# B45160514D.net
KiCad netlist of a schematic drawn in Altium Designer
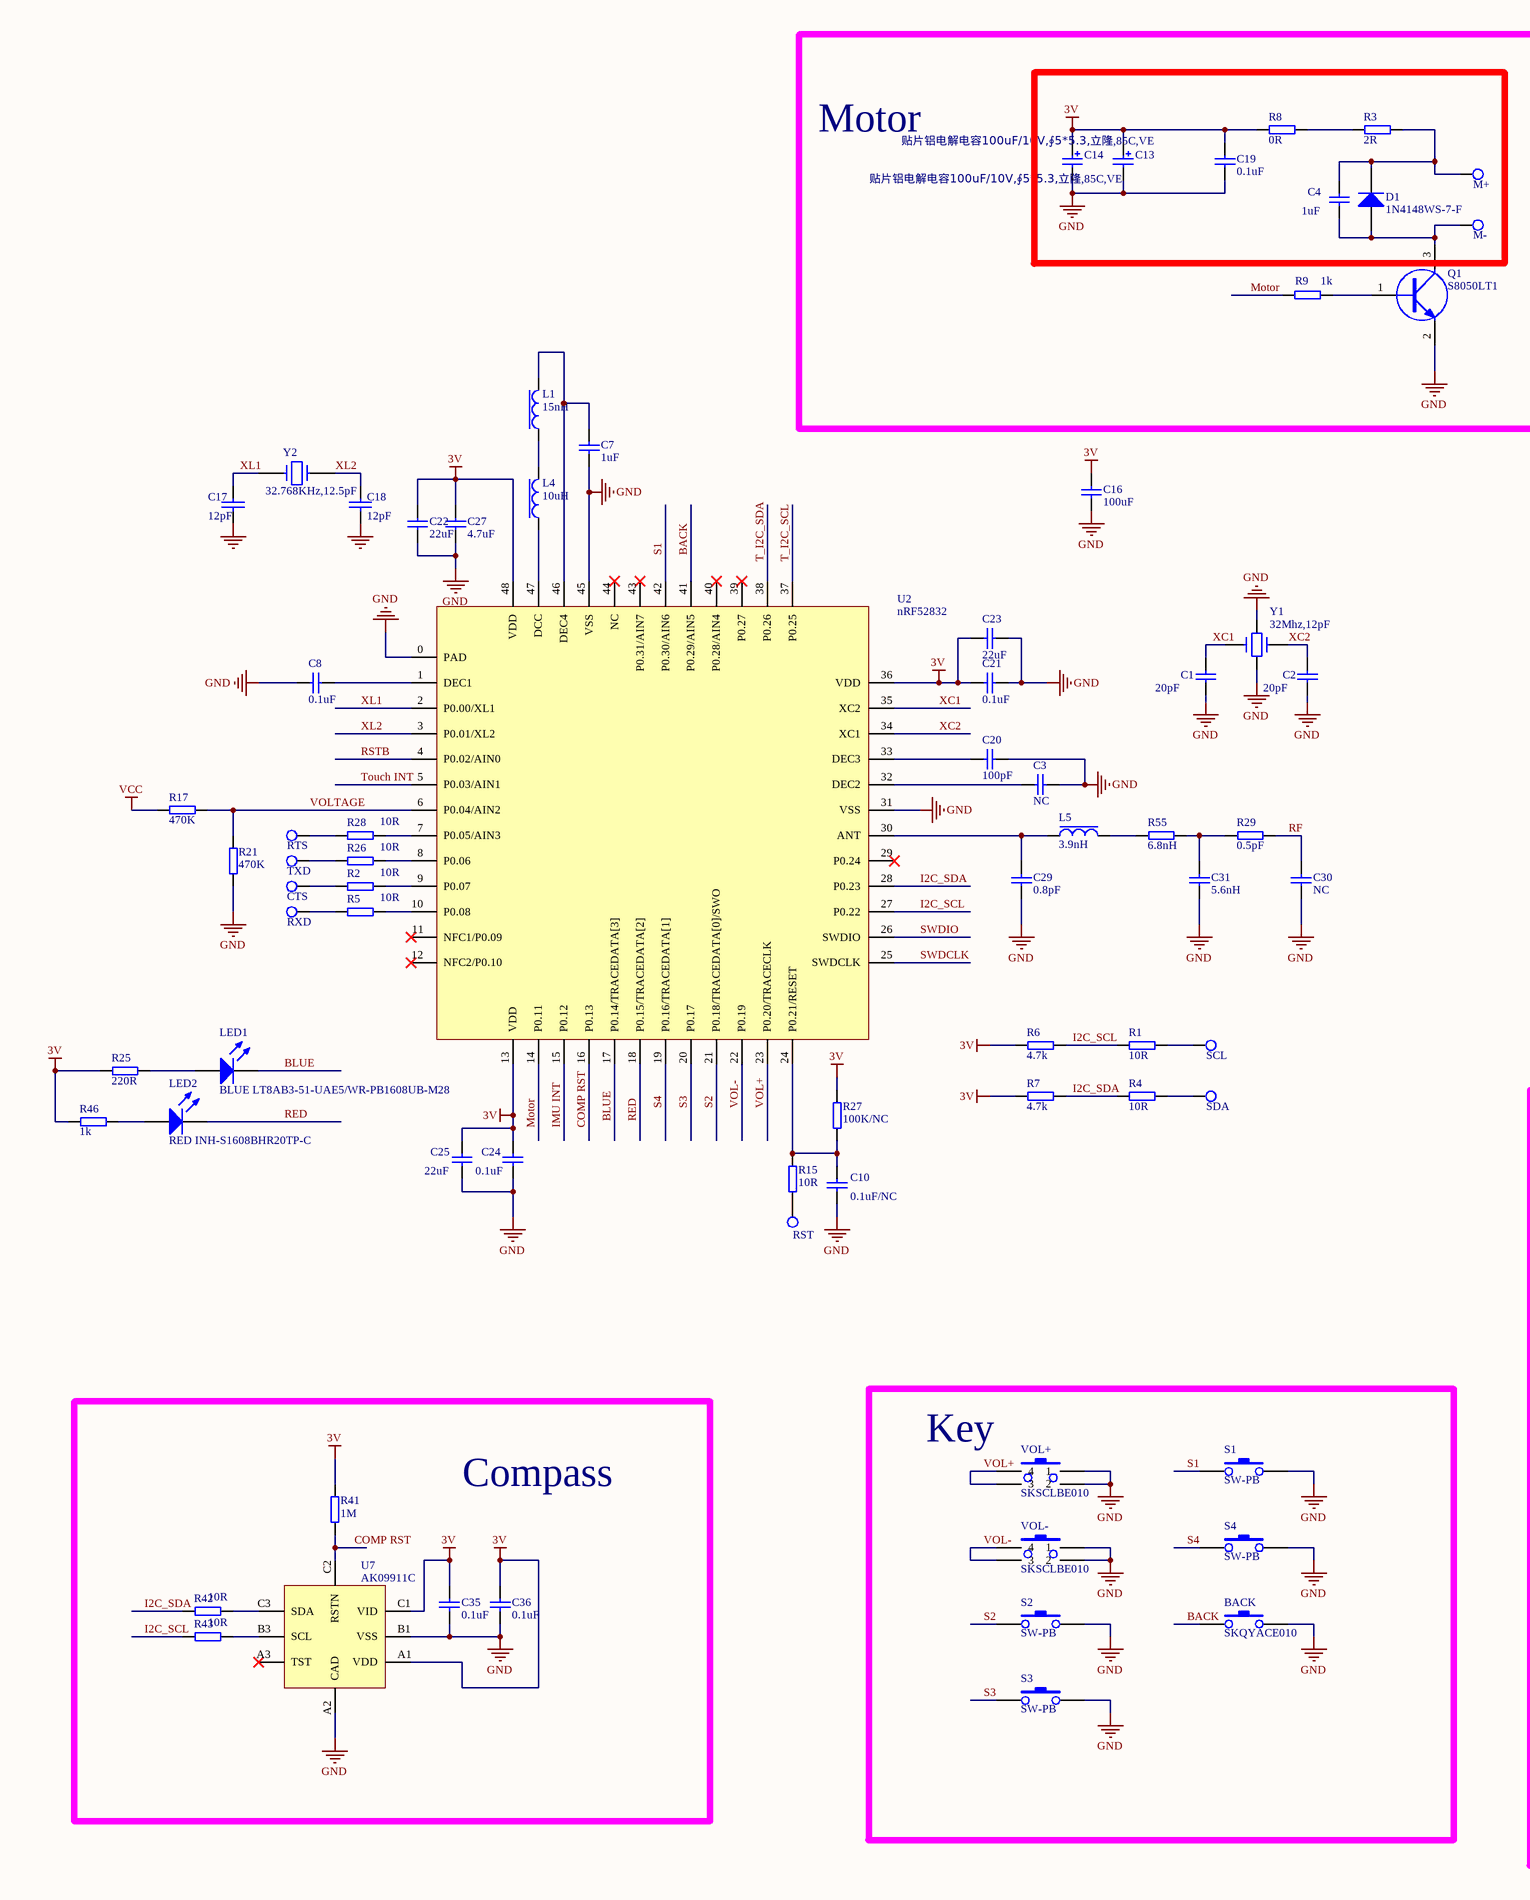
[diagram p0: B45160514D.SCHDOC, left]
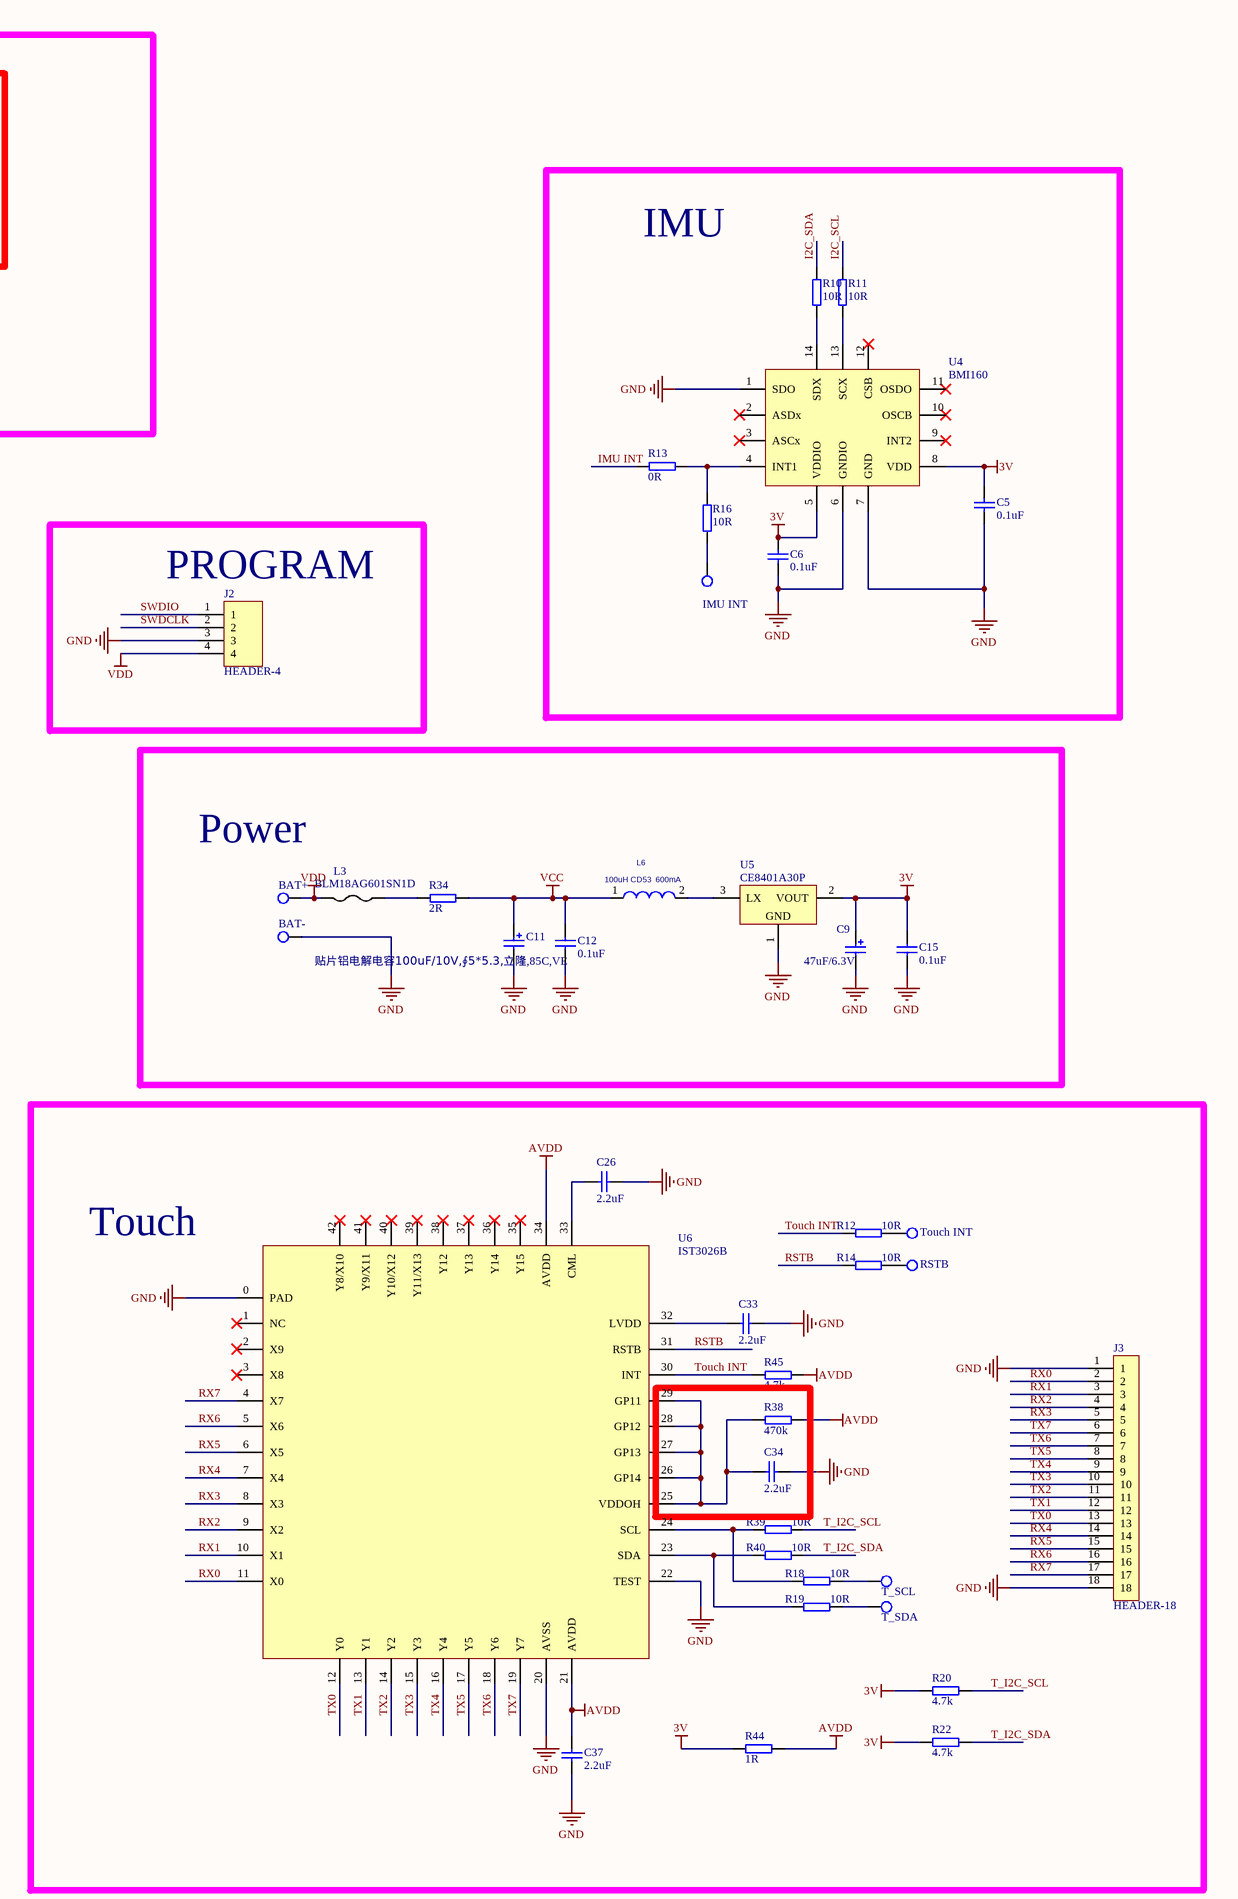
[diagram p1: B45160514D.SCHDOC, right]

(export (version "E")
  (design (tool "Eeschema 10.0.6"))
  (components
    (comp (ref "BACK") (value "SKQYACE010") (footprint "SKQYACE010") (libsource (lib "dusun") (part "SW-PB")))
    (comp (ref "BAT+") (value "TAP") (footprint "BAT") (libsource (lib "*") (part "TAP")))
    (comp (ref "BAT-") (value "TAP") (footprint "BAT") (libsource (lib "*") (part "TAP")))
    (comp (ref "C1") (value "20pF") (footprint "C-0402") (libsource (lib "dusun01-SCH") (part "CAP")))
    (comp (ref "C2") (value "20pF") (footprint "C-0402") (libsource (lib "dusun01-SCH") (part "CAP")))
    (comp (ref "C3") (value "NC") (footprint "C-0402") (libsource (lib "dusun01-SCH") (part "CAP")))
    (comp (ref "C4") (value "1uF") (footprint "C-0402") (libsource (lib "dusun01-SCH") (part "CAP")))
    (comp (ref "C5")
      (value "0.1uF")
      (footprint "C-0402")
      (description "capacitor 27 pF NPO , +/- 2 %, SMD case 0603")
      (fields
        (field (name "MANUFACTURER") "Generic Components")
        (field (name "PUBLISHER") "Altium Hobart Technology Centre")
      )
      (libsource (lib "Miscellaneous Devices") (part "Cap"))
    )
    (comp (ref "C6")
      (value "0.1uF")
      (footprint "C-0402")
      (description "capacitor 27 pF NPO , +/- 2 %, SMD case 0603")
      (fields
        (field (name "MANUFACTURER") "Generic Components")
        (field (name "PUBLISHER") "Altium Hobart Technology Centre")
      )
      (libsource (lib "Miscellaneous Devices") (part "Cap"))
    )
    (comp (ref "C7") (value "1uF") (footprint "C-0603") (libsource (lib "dusun01-SCH") (part "CAP")))
    (comp (ref "C8") (value "0.1uF") (footprint "C-0402") (libsource (lib "dusun01-SCH") (part "CAP")))
    (comp (ref "C9") (value "47uF/6.3V") (footprint "C-1206") (libsource (lib "dusun01-SCH") (part "CAP E")))
    (comp (ref "C10") (value "0.1uF/NC") (footprint "C-0402") (libsource (lib "dusun01-SCH") (part "CAP")))
    (comp (ref "C11")
      (value "贴片铝电解电容100uF/10V,∮5*5.3,立隆,85C,VE")
      (footprint "CAP_ALUM-C")
      (libsource (lib "dusun01-SCH") (part "CAP E"))
    )
    (comp (ref "C12") (value "0.1uF") (footprint "C-0603") (libsource (lib "dusun01-SCH") (part "CAP")))
    (comp (ref "C13")
      (value "贴片铝电解电容100uF/10V,∮5*5.3,立隆,85C,VE")
      (footprint "CAP_ALUM-C")
      (libsource (lib "dusun01-SCH") (part "CAP E"))
    )
    (comp (ref "C14")
      (value "贴片铝电解电容100uF/10V,∮5*5.3,立隆,85C,VE")
      (footprint "CAP_ALUM-C")
      (libsource (lib "dusun01-SCH") (part "CAP E"))
    )
    (comp (ref "C15") (value "0.1uF") (footprint "C-0603") (libsource (lib "dusun01-SCH") (part "CAP")))
    (comp (ref "C16") (value "100uF") (footprint "C-1206") (libsource (lib "dusun01-SCH") (part "CAP")))
    (comp (ref "C17")
      (value "12pF")
      (footprint "dusun01-pcb:C-0402")
      (description "Capacitor")
      (libsource (lib "*") (part "CAP"))
    )
    (comp (ref "C18")
      (value "12pF")
      (footprint "dusun01-pcb:C-0402")
      (description "Capacitor")
      (libsource (lib "*") (part "CAP"))
    )
    (comp (ref "C19") (value "0.1uF") (footprint "C-0603") (libsource (lib "dusun01-SCH") (part "CAP")))
    (comp (ref "C20") (value "100pF") (footprint "C-0402") (libsource (lib "dusun01-SCH") (part "CAP")))
    (comp (ref "C21") (value "0.1uF") (footprint "C-0402") (libsource (lib "dusun01-SCH") (part "CAP")))
    (comp (ref "C22") (value "22uF") (footprint "C-0805") (libsource (lib "dusun01-SCH") (part "CAP")))
    (comp (ref "C23") (value "22uF") (footprint "C-0805") (libsource (lib "dusun01-SCH") (part "CAP")))
    (comp (ref "C24") (value "0.1uF") (footprint "C-0402") (libsource (lib "dusun01-SCH") (part "CAP")))
    (comp (ref "C25") (value "22uF") (footprint "C-0805") (libsource (lib "dusun01-SCH") (part "CAP")))
    (comp (ref "C26") (value "2.2uF") (footprint "C-0402") (libsource (lib "dusun01-SCH") (part "CAP")))
    (comp (ref "C27") (value "4.7uF") (footprint "C-0603") (libsource (lib "dusun01-SCH") (part "CAP")))
    (comp (ref "C29") (value "0.8pF") (footprint "C-0402") (libsource (lib "dusun01-SCH") (part "CAP")))
    (comp (ref "C30") (value "NC") (footprint "C-0402") (libsource (lib "dusun01-SCH") (part "CAP")))
    (comp (ref "C31") (value "5.6nH") (footprint "C-0402") (libsource (lib "dusun01-SCH") (part "CAP")))
    (comp (ref "C33") (value "2.2uF") (footprint "C-0402") (libsource (lib "dusun01-SCH") (part "CAP")))
    (comp (ref "C34") (value "2.2uF") (footprint "C-0402") (libsource (lib "dusun01-SCH") (part "CAP")))
    (comp (ref "C35")
      (value "0.1uF")
      (footprint "C-0402")
      (description "capacitor 27 pF NPO , +/- 2 %, SMD case 0603")
      (fields
        (field (name "MANUFACTURER") "Generic Components")
        (field (name "PUBLISHER") "Altium Hobart Technology Centre")
      )
      (libsource (lib "Miscellaneous Devices") (part "Cap"))
    )
    (comp (ref "C36")
      (value "0.1uF")
      (footprint "C-0402")
      (description "capacitor 27 pF NPO , +/- 2 %, SMD case 0603")
      (fields
        (field (name "MANUFACTURER") "Generic Components")
        (field (name "PUBLISHER") "Altium Hobart Technology Centre")
      )
      (libsource (lib "Miscellaneous Devices") (part "Cap"))
    )
    (comp (ref "C37") (value "2.2uF") (footprint "C-0402") (libsource (lib "dusun01-SCH") (part "CAP")))
    (comp (ref "CTS") (value "TAP") (footprint "TS-1.0") (libsource (lib "dusun01-SCH") (part "TAP")))
    (comp (ref "D1")
      (value "1N4148WS-7-F")
      (footprint "SOD-323")
      (libsource (lib "dusun01-SCH") (part "DIODE"))
    )
    (comp (ref "IMU INT") (value "TAP") (footprint "TS-1.0") (libsource (lib "dusun01-SCH") (part "TAP")))
    (comp (ref "J2")
      (value "HEADER-4")
      (footprint "PH-4-2.0")
      (libsource (lib "dusun01-SCH") (part "HEADER-4"))
    )
    (comp (ref "J3")
      (value "HEADER-18")
      (footprint "0.5E-18PBX-P")
      (libsource (lib "dusun01-SCH") (part "HEADER-18"))
    )
    (comp (ref "L1") (value "15nH") (footprint "R-0402") (libsource (lib "dusun01-SCH") (part "INDUCTOR")))
    (comp (ref "L3")
      (value "BLM18AG601SN1D")
      (footprint "dusun01-pcb:R-0603")
      (libsource (lib "*") (part "Inductance"))
    )
    (comp (ref "L4")
      (value "10uH")
      (footprint "dusun02-pcb:R-0805")
      (libsource (lib "dusun01-SCH") (part "INDUCTOR"))
    )
    (comp (ref "L5") (value "3.9nH") (footprint "R-0402") (libsource (lib "dusun01-SCH") (part "INDUCTOR")))
    (comp (ref "L6")
      (value "100uH CD53  600mA")
      (footprint "FPI0503F-101M")
      (libsource (lib "*") (part "INDUCTOR_Dup1"))
    )
    (comp (ref "LED1")
      (value "BLUE LT8AB3-51-UAE5/WR-PB1608UB-M28")
      (footprint "LED-0603")
      (libsource (lib "dusun01-SCH") (part "LED"))
    )
    (comp (ref "LED2")
      (value "RED INH-S1608BHR20TP-C")
      (footprint "LED-0603")
      (libsource (lib "dusun01-SCH") (part "LED"))
    )
    (comp (ref "M+") (value "TAP") (footprint "TS-1.5*2") (libsource (lib "dusun01-SCH") (part "TAP")))
    (comp (ref "M-") (value "TAP") (footprint "TS-1.5*2") (libsource (lib "dusun01-SCH") (part "TAP")))
    (comp (ref "Q1")
      (value "S8050LT1")
      (footprint "SOT-23")
      (description "NPN型晶体管")
      (libsource (lib "dusun01-SCH") (part "NPN"))
    )
    (comp (ref "R1") (value "10R") (footprint "R-0402") (libsource (lib "dusun01-SCH") (part "RES")))
    (comp (ref "R2") (value "10R") (footprint "R-0402") (libsource (lib "dusun01-SCH") (part "RES")))
    (comp (ref "R3") (value "2R") (footprint "R-0805") (libsource (lib "dusun01-SCH") (part "RES")))
    (comp (ref "R4") (value "10R") (footprint "R-0402") (libsource (lib "dusun01-SCH") (part "RES")))
    (comp (ref "R5") (value "10R") (footprint "R-0402") (libsource (lib "dusun01-SCH") (part "RES")))
    (comp (ref "R6") (value "4.7k") (footprint "R-0402") (libsource (lib "dusun01-SCH") (part "RES")))
    (comp (ref "R7") (value "4.7k") (footprint "R-0402") (libsource (lib "dusun01-SCH") (part "RES")))
    (comp (ref "R8") (value "0R") (footprint "R-0805") (libsource (lib "dusun01-SCH") (part "RES")))
    (comp (ref "R9") (value "1k") (footprint "R-0402") (libsource (lib "dusun01-SCH") (part "RES")))
    (comp (ref "R10") (value "10R") (footprint "R-0402") (libsource (lib "dusun01-SCH") (part "RES")))
    (comp (ref "R11") (value "10R") (footprint "R-0402") (libsource (lib "dusun01-SCH") (part "RES")))
    (comp (ref "R12") (value "10R") (footprint "R-0402") (libsource (lib "dusun01-SCH") (part "RES")))
    (comp (ref "R13") (value "0R") (footprint "R-0402") (libsource (lib "dusun01-SCH") (part "RES")))
    (comp (ref "R14") (value "10R") (footprint "R-0402") (libsource (lib "dusun01-SCH") (part "RES")))
    (comp (ref "R15") (value "10R") (footprint "R-0402") (libsource (lib "dusun01-SCH") (part "RES")))
    (comp (ref "R16") (value "10R") (footprint "R-0402") (libsource (lib "dusun01-SCH") (part "RES")))
    (comp (ref "R17") (value "470K") (footprint "R-0402") (libsource (lib "dusun01-SCH") (part "RES")))
    (comp (ref "R18") (value "10R") (footprint "R-0402") (libsource (lib "dusun01-SCH") (part "RES")))
    (comp (ref "R19") (value "10R") (footprint "R-0402") (libsource (lib "dusun01-SCH") (part "RES")))
    (comp (ref "R20") (value "4.7k") (footprint "R-0402") (libsource (lib "dusun01-SCH") (part "RES")))
    (comp (ref "R21") (value "470K") (footprint "R-0402") (libsource (lib "dusun01-SCH") (part "RES")))
    (comp (ref "R22") (value "4.7k") (footprint "R-0402") (libsource (lib "dusun01-SCH") (part "RES")))
    (comp (ref "R25") (value "220R") (footprint "R-0603") (libsource (lib "dusun01-SCH") (part "RES")))
    (comp (ref "R26") (value "10R") (footprint "R-0402") (libsource (lib "dusun01-SCH") (part "RES")))
    (comp (ref "R27") (value "100K/NC") (footprint "R-0402") (libsource (lib "dusun01-SCH") (part "RES")))
    (comp (ref "R28") (value "10R") (footprint "R-0402") (libsource (lib "dusun01-SCH") (part "RES")))
    (comp (ref "R29") (value "0.5pF") (footprint "R-0402") (libsource (lib "dusun01-SCH") (part "RES")))
    (comp (ref "R34") (value "2R") (footprint "R-0603") (libsource (lib "dusun01-SCH") (part "RES")))
    (comp (ref "R38") (value "470k") (footprint "R-0402") (libsource (lib "dusun01-SCH") (part "RES")))
    (comp (ref "R39") (value "10R") (footprint "R-0402") (libsource (lib "dusun01-SCH") (part "RES")))
    (comp (ref "R40") (value "10R") (footprint "R-0402") (libsource (lib "dusun01-SCH") (part "RES")))
    (comp (ref "R41") (value "1M") (footprint "R-0402") (libsource (lib "dusun01-SCH") (part "RES")))
    (comp (ref "R42") (value "10R") (footprint "R-0402") (libsource (lib "dusun01-SCH") (part "RES")))
    (comp (ref "R43") (value "10R") (footprint "R-0402") (libsource (lib "dusun01-SCH") (part "RES")))
    (comp (ref "R44") (value "1R") (footprint "R-0402") (libsource (lib "dusun01-SCH") (part "RES")))
    (comp (ref "R45") (value "4.7k") (footprint "R-0402") (libsource (lib "dusun01-SCH") (part "RES")))
    (comp (ref "R46") (value "1k") (footprint "R-0603") (libsource (lib "dusun01-SCH") (part "RES")))
    (comp (ref "R55") (value "6.8nH") (footprint "R-0402") (libsource (lib "dusun01-SCH") (part "RES")))
    (comp (ref "RST") (value "TAP") (footprint "TS-1.0") (libsource (lib "dusun01-SCH") (part "TAP")))
    (comp (ref "RSTB") (value "TAP") (footprint "TS-1.0") (libsource (lib "dusun01-SCH") (part "TAP")))
    (comp (ref "RTS") (value "TAP") (footprint "TS-1.0") (libsource (lib "dusun01-SCH") (part "TAP")))
    (comp (ref "RXD") (value "TAP") (footprint "TS-1.0") (libsource (lib "dusun01-SCH") (part "TAP")))
    (comp (ref "S1") (value "SW-PB") (footprint "K mat D5") (libsource (lib "dusun") (part "SW-PB")))
    (comp (ref "S2") (value "SW-PB") (footprint "K mat D5") (libsource (lib "dusun") (part "SW-PB")))
    (comp (ref "S3") (value "SW-PB") (footprint "K mat D5") (libsource (lib "dusun") (part "SW-PB")))
    (comp (ref "S4") (value "SW-PB") (footprint "K mat D5") (libsource (lib "dusun") (part "SW-PB")))
    (comp (ref "SCL") (value "TAP") (footprint "TS-1.0") (libsource (lib "dusun01-SCH") (part "TAP")))
    (comp (ref "SDA") (value "TAP") (footprint "TS-1.0") (libsource (lib "dusun01-SCH") (part "TAP")))
    (comp (ref "Touch INT") (value "TAP") (footprint "TS-1.0") (libsource (lib "dusun01-SCH") (part "TAP")))
    (comp (ref "TXD") (value "TAP") (footprint "TS-1.0") (libsource (lib "dusun01-SCH") (part "TAP")))
    (comp (ref "T_SCL") (value "TAP") (footprint "TS-1.0") (libsource (lib "dusun01-SCH") (part "TAP")))
    (comp (ref "T_SDA") (value "TAP") (footprint "TS-1.0") (libsource (lib "dusun01-SCH") (part "TAP")))
    (comp (ref "U2")
      (value "nRF52832")
      (footprint "QFN-48-6*6-0.4")
      (libsource (lib "dusun01-SCH") (part "nRF52832"))
    )
    (comp (ref "U4") (value "BMI160") (footprint "LGA14") (libsource (lib "dusun01-SCH") (part "BMI160")))
    (comp (ref "U5")
      (value "CE8401A30P")
      (footprint "dusun01-pcb:SOT89")
      (libsource (lib "dusun01-SCH") (part "CE8401A33P"))
    )
    (comp (ref "U6")
      (value "IST3026B")
      (footprint "uTQFN-42-4.5*4.5")
      (libsource (lib "dusun01-SCH") (part "IST3026B"))
    )
    (comp (ref "U7")
      (value "AK09911C")
      (footprint "AK09911C")
      (libsource (lib "dusun01-SCH") (part "AK09911C"))
    )
    (comp (ref "VOL+")
      (value "SKSCLBE010")
      (footprint "SKSCLBE010")
      (libsource (lib "dusun01-SCH") (part "SW-PB4"))
    )
    (comp (ref "VOL-")
      (value "SKSCLBE010")
      (footprint "SKSCLBE010")
      (libsource (lib "dusun01-SCH") (part "SW-PB4"))
    )
    (comp (ref "Y1")
      (value "32Mhz,12pF")
      (footprint "XD3225-1-12M-125M")
      (libsource (lib "dusun01-SCH") (part "CRYSTAL4"))
    )
    (comp (ref "Y2")
      (value "32.768KHz,12.5pF")
      (footprint "32.768Khz-3215")
      (libsource (lib "dusun01-SCH") (part "CRYSTAL2"))
    )
  )
  (nets
    (net (code "1") (name "/BACK") (class "Default")
      (node (ref "BACK") (pin "2") (pinfunction "2_2") (pintype "passive"))
      (node (ref "U2") (pin "41") (pinfunction "P0.29/AIN5_41") (pintype "passive"))
    )
    (net (code "2") (name "/BLUE") (class "Default")
      (node (ref "LED1") (pin "2") (pinfunction "2_2") (pintype "passive"))
      (node (ref "U2") (pin "17") (pinfunction "P0.14/TRACEDATA[3]_17") (pintype "passive"))
    )
    (net (code "3") (name "/COMP RST") (class "Default")
      (node (ref "R41") (pin "2") (pinfunction "2_2") (pintype "passive"))
      (node (ref "U2") (pin "16") (pinfunction "P0.13_16") (pintype "passive"))
      (node (ref "U7") (pin "C2") (pinfunction "RSTN_C2") (pintype "passive"))
    )
    (net (code "4") (name "/I2C_SCL") (class "Default")
      (node (ref "R1") (pin "1") (pinfunction "1_1") (pintype "passive"))
      (node (ref "R11") (pin "2") (pinfunction "2_2") (pintype "passive"))
      (node (ref "R43") (pin "1") (pinfunction "1_1") (pintype "passive"))
      (node (ref "R6") (pin "2") (pinfunction "2_2") (pintype "passive"))
      (node (ref "U2") (pin "27") (pinfunction "P0.22_27") (pintype "passive"))
    )
    (net (code "5") (name "/I2C_SDA") (class "Default")
      (node (ref "R10") (pin "2") (pinfunction "2_2") (pintype "passive"))
      (node (ref "R4") (pin "1") (pinfunction "1_1") (pintype "passive"))
      (node (ref "R42") (pin "1") (pinfunction "1_1") (pintype "passive"))
      (node (ref "R7") (pin "2") (pinfunction "2_2") (pintype "passive"))
      (node (ref "U2") (pin "28") (pinfunction "P0.23_28") (pintype "passive"))
    )
    (net (code "6") (name "/IMU INT") (class "Default")
      (node (ref "R13") (pin "1") (pinfunction "1_1") (pintype "passive"))
      (node (ref "U2") (pin "15") (pinfunction "P0.12_15") (pintype "passive"))
    )
    (net (code "7") (name "/Motor") (class "Default")
      (node (ref "R9") (pin "1") (pinfunction "1_1") (pintype "passive"))
      (node (ref "U2") (pin "14") (pinfunction "P0.11_14") (pintype "passive"))
    )
    (net (code "8") (name "/RED") (class "Default")
      (node (ref "LED2") (pin "2") (pinfunction "2_2") (pintype "passive"))
      (node (ref "U2") (pin "18") (pinfunction "P0.15/TRACEDATA[2]_18") (pintype "passive"))
    )
    (net (code "9") (name "/RF") (class "Default")
      (node (ref "C30") (pin "1") (pinfunction "1_1") (pintype "passive"))
      (node (ref "R29") (pin "2") (pinfunction "2_2") (pintype "passive"))
    )
    (net (code "10") (name "/RSTB") (class "Default")
      (node (ref "R14") (pin "1") (pinfunction "1_1") (pintype "passive"))
      (node (ref "U2") (pin "4") (pinfunction "P0.02/AIN0_4") (pintype "passive"))
      (node (ref "U6") (pin "31") (pinfunction "RSTB_31") (pintype "passive"))
    )
    (net (code "11") (name "/RX0") (class "Default")
      (node (ref "J3") (pin "2") (pinfunction "2_2") (pintype "passive"))
      (node (ref "U6") (pin "11") (pinfunction "X0_11") (pintype "passive"))
    )
    (net (code "12") (name "/RX1") (class "Default")
      (node (ref "J3") (pin "3") (pinfunction "3_3") (pintype "passive"))
      (node (ref "U6") (pin "10") (pinfunction "X1_10") (pintype "passive"))
    )
    (net (code "13") (name "/RX2") (class "Default")
      (node (ref "J3") (pin "4") (pinfunction "4_4") (pintype "passive"))
      (node (ref "U6") (pin "9") (pinfunction "X2_9") (pintype "passive"))
    )
    (net (code "14") (name "/RX3") (class "Default")
      (node (ref "J3") (pin "5") (pinfunction "5_5") (pintype "passive"))
      (node (ref "U6") (pin "8") (pinfunction "X3_8") (pintype "passive"))
    )
    (net (code "15") (name "/RX4") (class "Default")
      (node (ref "J3") (pin "14") (pinfunction "14_14") (pintype "passive"))
      (node (ref "U6") (pin "7") (pinfunction "X4_7") (pintype "passive"))
    )
    (net (code "16") (name "/RX5") (class "Default")
      (node (ref "J3") (pin "15") (pinfunction "15_15") (pintype "passive"))
      (node (ref "U6") (pin "6") (pinfunction "X5_6") (pintype "passive"))
    )
    (net (code "17") (name "/RX6") (class "Default")
      (node (ref "J3") (pin "16") (pinfunction "16_16") (pintype "passive"))
      (node (ref "U6") (pin "5") (pinfunction "X6_5") (pintype "passive"))
    )
    (net (code "18") (name "/RX7") (class "Default")
      (node (ref "J3") (pin "17") (pinfunction "17_17") (pintype "passive"))
      (node (ref "U6") (pin "4") (pinfunction "X7_4") (pintype "passive"))
    )
    (net (code "19") (name "/S1") (class "Default")
      (node (ref "S1") (pin "1") (pinfunction "1_1") (pintype "passive"))
      (node (ref "U2") (pin "42") (pinfunction "P0.30/AIN6_42") (pintype "passive"))
    )
    (net (code "20") (name "/S2") (class "Default")
      (node (ref "S2") (pin "1") (pinfunction "1_1") (pintype "passive"))
      (node (ref "U2") (pin "21") (pinfunction "P0.18/TRACEDATA[0]/SWO_21") (pintype "passive"))
    )
    (net (code "21") (name "/S3") (class "Default")
      (node (ref "S3") (pin "2") (pinfunction "2_2") (pintype "passive"))
      (node (ref "U2") (pin "20") (pinfunction "P0.17_20") (pintype "passive"))
    )
    (net (code "22") (name "/S4") (class "Default")
      (node (ref "S4") (pin "1") (pinfunction "1_1") (pintype "passive"))
      (node (ref "U2") (pin "19") (pinfunction "P0.16/TRACEDATA[1]_19") (pintype "passive"))
    )
    (net (code "23") (name "/SWDCLK") (class "Default")
      (node (ref "J2") (pin "2") (pinfunction "2_2") (pintype "passive"))
      (node (ref "U2") (pin "25") (pinfunction "SWDCLK_25") (pintype "passive"))
    )
    (net (code "24") (name "/SWDIO") (class "Default")
      (node (ref "J2") (pin "1") (pinfunction "1_1") (pintype "passive"))
      (node (ref "U2") (pin "26") (pinfunction "SWDIO_26") (pintype "passive"))
    )
    (net (code "25") (name "/TX0") (class "Default")
      (node (ref "J3") (pin "13") (pinfunction "13_13") (pintype "passive"))
      (node (ref "U6") (pin "12") (pinfunction "Y0_12") (pintype "passive"))
    )
    (net (code "26") (name "/TX1") (class "Default")
      (node (ref "J3") (pin "12") (pinfunction "12_12") (pintype "passive"))
      (node (ref "U6") (pin "13") (pinfunction "Y1_13") (pintype "passive"))
    )
    (net (code "27") (name "/TX2") (class "Default")
      (node (ref "J3") (pin "11") (pinfunction "11_11") (pintype "passive"))
      (node (ref "U6") (pin "14") (pinfunction "Y2_14") (pintype "passive"))
    )
    (net (code "28") (name "/TX3") (class "Default")
      (node (ref "J3") (pin "10") (pinfunction "10_10") (pintype "passive"))
      (node (ref "U6") (pin "15") (pinfunction "Y3_15") (pintype "passive"))
    )
    (net (code "29") (name "/TX4") (class "Default")
      (node (ref "J3") (pin "9") (pinfunction "9_9") (pintype "passive"))
      (node (ref "U6") (pin "16") (pinfunction "Y4_16") (pintype "passive"))
    )
    (net (code "30") (name "/TX5") (class "Default")
      (node (ref "J3") (pin "8") (pinfunction "8_8") (pintype "passive"))
      (node (ref "U6") (pin "17") (pinfunction "Y5_17") (pintype "passive"))
    )
    (net (code "31") (name "/TX6") (class "Default")
      (node (ref "J3") (pin "7") (pinfunction "7_7") (pintype "passive"))
      (node (ref "U6") (pin "18") (pinfunction "Y6_18") (pintype "passive"))
    )
    (net (code "32") (name "/TX7") (class "Default")
      (node (ref "J3") (pin "6") (pinfunction "6_6") (pintype "passive"))
      (node (ref "U6") (pin "19") (pinfunction "Y7_19") (pintype "passive"))
    )
    (net (code "33") (name "/T_I2C_SCL") (class "Default")
      (node (ref "R20") (pin "2") (pinfunction "2_2") (pintype "passive"))
      (node (ref "R39") (pin "2") (pinfunction "2_2") (pintype "passive"))
      (node (ref "U2") (pin "37") (pinfunction "P0.25_37") (pintype "passive"))
    )
    (net (code "34") (name "/T_I2C_SDA") (class "Default")
      (node (ref "R22") (pin "2") (pinfunction "2_2") (pintype "passive"))
      (node (ref "R40") (pin "2") (pinfunction "2_2") (pintype "passive"))
      (node (ref "U2") (pin "38") (pinfunction "P0.26_38") (pintype "passive"))
    )
    (net (code "35") (name "/Touch INT") (class "Default")
      (node (ref "R12") (pin "1") (pinfunction "1_1") (pintype "passive"))
      (node (ref "R45") (pin "1") (pinfunction "1_1") (pintype "passive"))
      (node (ref "U2") (pin "5") (pinfunction "P0.03/AIN1_5") (pintype "passive"))
      (node (ref "U6") (pin "30") (pinfunction "INT_30") (pintype "passive"))
    )
    (net (code "36") (name "/VOL+") (class "Default")
      (node (ref "U2") (pin "23") (pinfunction "P0.20/TRACECLK_23") (pintype "passive"))
      (node (ref "VOL+") (pin "3") (pinfunction "3_3") (pintype "passive"))
      (node (ref "VOL+") (pin "4") (pinfunction "4_4") (pintype "passive"))
    )
    (net (code "37") (name "/VOL-") (class "Default")
      (node (ref "U2") (pin "22") (pinfunction "P0.19_22") (pintype "passive"))
      (node (ref "VOL-") (pin "3") (pinfunction "3_3") (pintype "passive"))
      (node (ref "VOL-") (pin "4") (pinfunction "4_4") (pintype "passive"))
    )
    (net (code "38") (name "/VOLTAGE") (class "Default")
      (node (ref "R17") (pin "2") (pinfunction "2_2") (pintype "passive"))
      (node (ref "R21") (pin "2") (pinfunction "2_2") (pintype "passive"))
      (node (ref "U2") (pin "6") (pinfunction "P0.04/AIN2_6") (pintype "passive"))
    )
    (net (code "39") (name "/XC1") (class "Default")
      (node (ref "C1") (pin "1") (pinfunction "1_1") (pintype "passive"))
      (node (ref "U2") (pin "35") (pinfunction "XC2_35") (pintype "passive"))
      (node (ref "Y1") (pin "1") (pinfunction "1_1") (pintype "passive"))
    )
    (net (code "40") (name "/XC2") (class "Default")
      (node (ref "C2") (pin "1") (pinfunction "1_1") (pintype "passive"))
      (node (ref "U2") (pin "34") (pinfunction "XC1_34") (pintype "passive"))
      (node (ref "Y1") (pin "2") (pinfunction "2_2") (pintype "passive"))
    )
    (net (code "41") (name "/XL1") (class "Default")
      (node (ref "C17") (pin "1") (pinfunction "1_1") (pintype "passive"))
      (node (ref "U2") (pin "2") (pinfunction "P0.00/XL1_2") (pintype "passive"))
      (node (ref "Y2") (pin "1") (pinfunction "1_1") (pintype "passive"))
    )
    (net (code "42") (name "/XL2") (class "Default")
      (node (ref "C18") (pin "1") (pinfunction "1_1") (pintype "passive"))
      (node (ref "U2") (pin "3") (pinfunction "P0.01/XL2_3") (pintype "passive"))
      (node (ref "Y2") (pin "2") (pinfunction "2_2") (pintype "passive"))
    )
    (net (code "43") (name "3V") (class "Default")
      (node (ref "C13") (pin "1") (pinfunction "1_1") (pintype "passive"))
      (node (ref "C14") (pin "1") (pinfunction "1_1") (pintype "passive"))
      (node (ref "C15") (pin "1") (pinfunction "1_1") (pintype "passive"))
      (node (ref "C16") (pin "1") (pinfunction "1_1") (pintype "passive"))
      (node (ref "C19") (pin "1") (pinfunction "1_1") (pintype "passive"))
      (node (ref "C21") (pin "1") (pinfunction "1_1") (pintype "passive"))
      (node (ref "C22") (pin "2") (pinfunction "2_2") (pintype "passive"))
      (node (ref "C23") (pin "1") (pinfunction "1_1") (pintype "passive"))
      (node (ref "C24") (pin "1") (pinfunction "1_1") (pintype "passive"))
      (node (ref "C25") (pin "1") (pinfunction "1_1") (pintype "passive"))
      (node (ref "C27") (pin "1") (pinfunction "1_1") (pintype "passive"))
      (node (ref "C35") (pin "1") (pinfunction "1_1") (pintype "passive"))
      (node (ref "C36") (pin "2") (pinfunction "2_2") (pintype "passive"))
      (node (ref "C5") (pin "1") (pinfunction "1_1") (pintype "passive"))
      (node (ref "C6") (pin "1") (pinfunction "1_1") (pintype "passive"))
      (node (ref "C9") (pin "1") (pinfunction "1_1") (pintype "passive"))
      (node (ref "R20") (pin "1") (pinfunction "1_1") (pintype "passive"))
      (node (ref "R22") (pin "1") (pinfunction "1_1") (pintype "passive"))
      (node (ref "R25") (pin "2") (pinfunction "2_2") (pintype "passive"))
      (node (ref "R27") (pin "1") (pinfunction "1_1") (pintype "passive"))
      (node (ref "R41") (pin "1") (pinfunction "1_1") (pintype "passive"))
      (node (ref "R44") (pin "1") (pinfunction "1_1") (pintype "passive"))
      (node (ref "R46") (pin "2") (pinfunction "2_2") (pintype "passive"))
      (node (ref "R6") (pin "1") (pinfunction "1_1") (pintype "passive"))
      (node (ref "R7") (pin "1") (pinfunction "1_1") (pintype "passive"))
      (node (ref "R8") (pin "2") (pinfunction "2_2") (pintype "passive"))
      (node (ref "U2") (pin "13") (pinfunction "VDD_13") (pintype "passive"))
      (node (ref "U2") (pin "36") (pinfunction "VDD_36") (pintype "passive"))
      (node (ref "U2") (pin "48") (pinfunction "VDD_48") (pintype "passive"))
      (node (ref "U4") (pin "5") (pinfunction "VDDIO_5") (pintype "passive"))
      (node (ref "U4") (pin "8") (pinfunction "VDD_8") (pintype "passive"))
      (node (ref "U5") (pin "2") (pinfunction "VOUT_2") (pintype "passive"))
      (node (ref "U7") (pin "A1") (pinfunction "VDD_A1") (pintype "passive"))
      (node (ref "U7") (pin "C1") (pinfunction "VID_C1") (pintype "passive"))
    )
    (net (code "44") (name "AVDD") (class "Default")
      (node (ref "C37") (pin "1") (pinfunction "1_1") (pintype "passive"))
      (node (ref "R38") (pin "2") (pinfunction "2_2") (pintype "passive"))
      (node (ref "R44") (pin "2") (pinfunction "2_2") (pintype "passive"))
      (node (ref "R45") (pin "2") (pinfunction "2_2") (pintype "passive"))
      (node (ref "U6") (pin "21") (pinfunction "AVDD_21") (pintype "passive"))
      (node (ref "U6") (pin "34") (pinfunction "AVDD_34") (pintype "passive"))
    )
    (net (code "45") (name "GND") (class "Default")
      (node (ref "BACK") (pin "1") (pinfunction "1_1") (pintype "passive"))
      (node (ref "BAT-") (pin "1") (pinfunction "1_1") (pintype "passive"))
      (node (ref "C1") (pin "2") (pinfunction "2_2") (pintype "passive"))
      (node (ref "C10") (pin "2") (pinfunction "2_2") (pintype "passive"))
      (node (ref "C11") (pin "2") (pinfunction "2_2") (pintype "passive"))
      (node (ref "C12") (pin "2") (pinfunction "2_2") (pintype "passive"))
      (node (ref "C13") (pin "2") (pinfunction "2_2") (pintype "passive"))
      (node (ref "C14") (pin "2") (pinfunction "2_2") (pintype "passive"))
      (node (ref "C15") (pin "2") (pinfunction "2_2") (pintype "passive"))
      (node (ref "C16") (pin "2") (pinfunction "2_2") (pintype "passive"))
      (node (ref "C17") (pin "2") (pinfunction "2_2") (pintype "passive"))
      (node (ref "C18") (pin "2") (pinfunction "2_2") (pintype "passive"))
      (node (ref "C19") (pin "2") (pinfunction "2_2") (pintype "passive"))
      (node (ref "C2") (pin "2") (pinfunction "2_2") (pintype "passive"))
      (node (ref "C20") (pin "2") (pinfunction "2_2") (pintype "passive"))
      (node (ref "C21") (pin "2") (pinfunction "2_2") (pintype "passive"))
      (node (ref "C22") (pin "1") (pinfunction "1_1") (pintype "passive"))
      (node (ref "C23") (pin "2") (pinfunction "2_2") (pintype "passive"))
      (node (ref "C24") (pin "2") (pinfunction "2_2") (pintype "passive"))
      (node (ref "C25") (pin "2") (pinfunction "2_2") (pintype "passive"))
      (node (ref "C26") (pin "1") (pinfunction "1_1") (pintype "passive"))
      (node (ref "C27") (pin "2") (pinfunction "2_2") (pintype "passive"))
      (node (ref "C29") (pin "2") (pinfunction "2_2") (pintype "passive"))
      (node (ref "C3") (pin "2") (pinfunction "2_2") (pintype "passive"))
      (node (ref "C30") (pin "2") (pinfunction "2_2") (pintype "passive"))
      (node (ref "C31") (pin "2") (pinfunction "2_2") (pintype "passive"))
      (node (ref "C33") (pin "2") (pinfunction "2_2") (pintype "passive"))
      (node (ref "C34") (pin "2") (pinfunction "2_2") (pintype "passive"))
      (node (ref "C35") (pin "2") (pinfunction "2_2") (pintype "passive"))
      (node (ref "C36") (pin "1") (pinfunction "1_1") (pintype "passive"))
      (node (ref "C37") (pin "2") (pinfunction "2_2") (pintype "passive"))
      (node (ref "C5") (pin "2") (pinfunction "2_2") (pintype "passive"))
      (node (ref "C6") (pin "2") (pinfunction "2_2") (pintype "passive"))
      (node (ref "C7") (pin "1") (pinfunction "1_1") (pintype "passive"))
      (node (ref "C8") (pin "1") (pinfunction "1_1") (pintype "passive"))
      (node (ref "C9") (pin "2") (pinfunction "2_2") (pintype "passive"))
      (node (ref "J2") (pin "3") (pinfunction "3_3") (pintype "passive"))
      (node (ref "J3") (pin "1") (pinfunction "1_1") (pintype "passive"))
      (node (ref "J3") (pin "18") (pinfunction "18_18") (pintype "passive"))
      (node (ref "Q1") (pin "2") (pinfunction "e_2") (pintype "passive"))
      (node (ref "R21") (pin "1") (pinfunction "1_1") (pintype "passive"))
      (node (ref "S1") (pin "2") (pinfunction "2_2") (pintype "passive"))
      (node (ref "S2") (pin "2") (pinfunction "2_2") (pintype "passive"))
      (node (ref "S3") (pin "1") (pinfunction "1_1") (pintype "passive"))
      (node (ref "S4") (pin "2") (pinfunction "2_2") (pintype "passive"))
      (node (ref "U2") (pin "0") (pinfunction "PAD_0") (pintype "passive"))
      (node (ref "U2") (pin "31") (pinfunction "VSS_31") (pintype "passive"))
      (node (ref "U2") (pin "45") (pinfunction "VSS_45") (pintype "passive"))
      (node (ref "U4") (pin "1") (pinfunction "SDO_1") (pintype "passive"))
      (node (ref "U4") (pin "6") (pinfunction "GNDIO_6") (pintype "passive"))
      (node (ref "U4") (pin "7") (pinfunction "GND_7") (pintype "passive"))
      (node (ref "U5") (pin "1") (pinfunction "GND_1") (pintype "passive"))
      (node (ref "U6") (pin "0") (pinfunction "PAD_0") (pintype "passive"))
      (node (ref "U6") (pin "20") (pinfunction "AVSS_20") (pintype "passive"))
      (node (ref "U6") (pin "22") (pinfunction "TEST_22") (pintype "passive"))
      (node (ref "U7") (pin "A2") (pinfunction "CAD_A2") (pintype "passive"))
      (node (ref "U7") (pin "B1") (pinfunction "VSS_B1") (pintype "passive"))
      (node (ref "VOL+") (pin "1") (pinfunction "1_1") (pintype "passive"))
      (node (ref "VOL+") (pin "2") (pinfunction "2_2") (pintype "passive"))
      (node (ref "VOL-") (pin "1") (pinfunction "1_1") (pintype "passive"))
      (node (ref "VOL-") (pin "2") (pinfunction "2_2") (pintype "passive"))
      (node (ref "Y1") (pin "3") (pinfunction "3_3") (pintype "passive"))
    )
    (net (code "46") (name "Net-(C4-Pad1)") (class "Default")
      (node (ref "C4") (pin "1") (pinfunction "1_1") (pintype "passive"))
      (node (ref "D1") (pin "2") (pinfunction "2_2") (pintype "passive"))
      (node (ref "M+") (pin "1") (pinfunction "1_1") (pintype "passive"))
      (node (ref "R3") (pin "1") (pinfunction "1_1") (pintype "passive"))
    )
    (net (code "47") (name "Net-(C31-Pad1)") (class "Default")
      (node (ref "C31") (pin "1") (pinfunction "1_1") (pintype "passive"))
      (node (ref "R29") (pin "1") (pinfunction "1_1") (pintype "passive"))
      (node (ref "R55") (pin "2") (pinfunction "2_2") (pintype "passive"))
    )
    (net (code "48") (name "Net-(CTS-Pad1)") (class "Default")
      (node (ref "CTS") (pin "1") (pinfunction "1_1") (pintype "passive"))
      (node (ref "R2") (pin "2") (pinfunction "2_2") (pintype "passive"))
    )
    (net (code "49") (name "Net-(IMU INT-Pad1)") (class "Default")
      (node (ref "IMU INT") (pin "1") (pinfunction "1_1") (pintype "passive"))
      (node (ref "R16") (pin "1") (pinfunction "1_1") (pintype "passive"))
    )
    (net (code "50") (name "Net-(L1-Pad1)") (class "Default")
      (node (ref "L1") (pin "1") (pinfunction "1_1") (pintype "passive"))
      (node (ref "L4") (pin "2") (pinfunction "2_2") (pintype "passive"))
    )
    (net (code "51") (name "Net-(L3-Pad1)") (class "Default")
      (node (ref "L3") (pin "1") (pintype "passive"))
      (node (ref "R34") (pin "2") (pinfunction "2_2") (pintype "passive"))
    )
    (net (code "52") (name "Net-(L5-Pad2)") (class "Default")
      (node (ref "L5") (pin "2") (pinfunction "2_2") (pintype "passive"))
      (node (ref "R55") (pin "1") (pinfunction "1_1") (pintype "passive"))
    )
    (net (code "53") (name "Net-(LED1-Pad1)") (class "Default")
      (node (ref "LED1") (pin "1") (pinfunction "1_1") (pintype "passive"))
      (node (ref "R25") (pin "1") (pinfunction "1_1") (pintype "passive"))
    )
    (net (code "54") (name "Net-(LED2-Pad1)") (class "Default")
      (node (ref "LED2") (pin "1") (pinfunction "1_1") (pintype "passive"))
      (node (ref "R46") (pin "1") (pinfunction "1_1") (pintype "passive"))
    )
    (net (code "55") (name "Net-(Q1-b)") (class "Default")
      (node (ref "Q1") (pin "1") (pinfunction "b_1") (pintype "passive"))
      (node (ref "R9") (pin "2") (pinfunction "2_2") (pintype "passive"))
    )
    (net (code "56") (name "Net-(Q1-c)") (class "Default")
      (node (ref "C4") (pin "2") (pinfunction "2_2") (pintype "passive"))
      (node (ref "D1") (pin "1") (pinfunction "1_1") (pintype "passive"))
      (node (ref "M-") (pin "1") (pinfunction "1_1") (pintype "passive"))
      (node (ref "Q1") (pin "3") (pinfunction "c_3") (pintype "passive"))
    )
    (net (code "57") (name "Net-(R1-Pad2)") (class "Default")
      (node (ref "R1") (pin "2") (pinfunction "2_2") (pintype "passive"))
      (node (ref "SCL") (pin "1") (pinfunction "1_1") (pintype "passive"))
    )
    (net (code "58") (name "Net-(R3-Pad2)") (class "Default")
      (node (ref "R3") (pin "2") (pinfunction "2_2") (pintype "passive"))
      (node (ref "R8") (pin "1") (pinfunction "1_1") (pintype "passive"))
    )
    (net (code "59") (name "Net-(R4-Pad2)") (class "Default")
      (node (ref "R4") (pin "2") (pinfunction "2_2") (pintype "passive"))
      (node (ref "SDA") (pin "1") (pinfunction "1_1") (pintype "passive"))
    )
    (net (code "60") (name "Net-(R5-Pad2)") (class "Default")
      (node (ref "R5") (pin "2") (pinfunction "2_2") (pintype "passive"))
      (node (ref "RXD") (pin "1") (pinfunction "1_1") (pintype "passive"))
    )
    (net (code "61") (name "Net-(R12-Pad2)") (class "Default")
      (node (ref "R12") (pin "2") (pinfunction "2_2") (pintype "passive"))
      (node (ref "Touch INT") (pin "1") (pinfunction "1_1") (pintype "passive"))
    )
    (net (code "62") (name "Net-(R14-Pad2)") (class "Default")
      (node (ref "R14") (pin "2") (pinfunction "2_2") (pintype "passive"))
      (node (ref "RSTB") (pin "1") (pinfunction "1_1") (pintype "passive"))
    )
    (net (code "63") (name "Net-(R15-Pad1)") (class "Default")
      (node (ref "R15") (pin "1") (pinfunction "1_1") (pintype "passive"))
      (node (ref "RST") (pin "1") (pinfunction "1_1") (pintype "passive"))
    )
    (net (code "64") (name "Net-(R18-Pad2)") (class "Default")
      (node (ref "R18") (pin "2") (pinfunction "2_2") (pintype "passive"))
      (node (ref "T_SCL") (pin "1") (pinfunction "1_1") (pintype "passive"))
    )
    (net (code "65") (name "Net-(R19-Pad2)") (class "Default")
      (node (ref "R19") (pin "2") (pinfunction "2_2") (pintype "passive"))
      (node (ref "T_SDA") (pin "1") (pinfunction "1_1") (pintype "passive"))
    )
    (net (code "66") (name "Net-(R26-Pad2)") (class "Default")
      (node (ref "R26") (pin "2") (pinfunction "2_2") (pintype "passive"))
      (node (ref "TXD") (pin "1") (pinfunction "1_1") (pintype "passive"))
    )
    (net (code "67") (name "Net-(R28-Pad2)") (class "Default")
      (node (ref "R28") (pin "2") (pinfunction "2_2") (pintype "passive"))
      (node (ref "RTS") (pin "1") (pinfunction "1_1") (pintype "passive"))
    )
    (net (code "68") (name "Net-(U2-ANT)") (class "Default")
      (node (ref "C29") (pin "1") (pinfunction "1_1") (pintype "passive"))
      (node (ref "L5") (pin "1") (pinfunction "1_1") (pintype "passive"))
      (node (ref "U2") (pin "30") (pinfunction "ANT_30") (pintype "passive"))
    )
    (net (code "69") (name "Net-(U2-DCC)") (class "Default")
      (node (ref "L4") (pin "1") (pinfunction "1_1") (pintype "passive"))
      (node (ref "U2") (pin "47") (pinfunction "DCC_47") (pintype "passive"))
    )
    (net (code "70") (name "Net-(U2-DEC1)") (class "Default")
      (node (ref "C8") (pin "2") (pinfunction "2_2") (pintype "passive"))
      (node (ref "U2") (pin "1") (pinfunction "DEC1_1") (pintype "passive"))
    )
    (net (code "71") (name "Net-(U2-DEC2)") (class "Default")
      (node (ref "C3") (pin "1") (pinfunction "1_1") (pintype "passive"))
      (node (ref "U2") (pin "32") (pinfunction "DEC2_32") (pintype "passive"))
    )
    (net (code "72") (name "Net-(U2-DEC3)") (class "Default")
      (node (ref "C20") (pin "1") (pinfunction "1_1") (pintype "passive"))
      (node (ref "U2") (pin "33") (pinfunction "DEC3_33") (pintype "passive"))
    )
    (net (code "73") (name "Net-(U2-DEC4)") (class "Default")
      (node (ref "C7") (pin "2") (pinfunction "2_2") (pintype "passive"))
      (node (ref "L1") (pin "2") (pinfunction "2_2") (pintype "passive"))
      (node (ref "U2") (pin "46") (pinfunction "DEC4_46") (pintype "passive"))
    )
    (net (code "74") (name "Net-(U2-P0.05{slash}AIN3)") (class "Default")
      (node (ref "R28") (pin "1") (pinfunction "1_1") (pintype "passive"))
      (node (ref "U2") (pin "7") (pinfunction "P0.05/AIN3_7") (pintype "passive"))
    )
    (net (code "75") (name "Net-(U2-P0.06)") (class "Default")
      (node (ref "R26") (pin "1") (pinfunction "1_1") (pintype "passive"))
      (node (ref "U2") (pin "8") (pinfunction "P0.06_8") (pintype "passive"))
    )
    (net (code "76") (name "Net-(U2-P0.07)") (class "Default")
      (node (ref "R2") (pin "1") (pinfunction "1_1") (pintype "passive"))
      (node (ref "U2") (pin "9") (pinfunction "P0.07_9") (pintype "passive"))
    )
    (net (code "77") (name "Net-(U2-P0.08)") (class "Default")
      (node (ref "R5") (pin "1") (pinfunction "1_1") (pintype "passive"))
      (node (ref "U2") (pin "10") (pinfunction "P0.08_10") (pintype "passive"))
    )
    (net (code "78") (name "Net-(U2-P0.21{slash}RESET)") (class "Default")
      (node (ref "C10") (pin "1") (pinfunction "1_1") (pintype "passive"))
      (node (ref "R15") (pin "2") (pinfunction "2_2") (pintype "passive"))
      (node (ref "R27") (pin "2") (pinfunction "2_2") (pintype "passive"))
      (node (ref "U2") (pin "24") (pinfunction "P0.21/RESET_24") (pintype "passive"))
    )
    (net (code "79") (name "Net-(U4-INT1)") (class "Default")
      (node (ref "R13") (pin "2") (pinfunction "2_2") (pintype "passive"))
      (node (ref "R16") (pin "2") (pinfunction "2_2") (pintype "passive"))
      (node (ref "U4") (pin "4") (pinfunction "INT1_4") (pintype "passive"))
    )
    (net (code "80") (name "Net-(U4-SCX)") (class "Default")
      (node (ref "R11") (pin "1") (pinfunction "1_1") (pintype "passive"))
      (node (ref "U4") (pin "13") (pinfunction "SCX_13") (pintype "passive"))
    )
    (net (code "81") (name "Net-(U4-SDX)") (class "Default")
      (node (ref "R10") (pin "1") (pinfunction "1_1") (pintype "passive"))
      (node (ref "U4") (pin "14") (pinfunction "SDX_14") (pintype "passive"))
    )
    (net (code "82") (name "Net-(U5-LX)") (class "Default")
      (node (ref "L6") (pin "2") (pinfunction "2_2") (pintype "passive"))
      (node (ref "U5") (pin "3") (pinfunction "LX_3") (pintype "passive"))
    )
    (net (code "83") (name "Net-(U6-CML)") (class "Default")
      (node (ref "C26") (pin "2") (pinfunction "2_2") (pintype "passive"))
      (node (ref "U6") (pin "33") (pinfunction "CML_33") (pintype "passive"))
    )
    (net (code "84") (name "Net-(U6-GP11)") (class "Default")
      (node (ref "C34") (pin "1") (pinfunction "1_1") (pintype "passive"))
      (node (ref "R38") (pin "1") (pinfunction "1_1") (pintype "passive"))
      (node (ref "U6") (pin "25") (pinfunction "VDDOH_25") (pintype "passive"))
      (node (ref "U6") (pin "26") (pinfunction "GP14_26") (pintype "passive"))
      (node (ref "U6") (pin "27") (pinfunction "GP13_27") (pintype "passive"))
      (node (ref "U6") (pin "28") (pinfunction "GP12_28") (pintype "passive"))
      (node (ref "U6") (pin "29") (pinfunction "GP11_29") (pintype "passive"))
    )
    (net (code "85") (name "Net-(U6-LVDD)") (class "Default")
      (node (ref "C33") (pin "1") (pinfunction "1_1") (pintype "passive"))
      (node (ref "U6") (pin "32") (pinfunction "LVDD_32") (pintype "passive"))
    )
    (net (code "86") (name "Net-(U6-SCL)") (class "Default")
      (node (ref "R18") (pin "1") (pinfunction "1_1") (pintype "passive"))
      (node (ref "R39") (pin "1") (pinfunction "1_1") (pintype "passive"))
      (node (ref "U6") (pin "24") (pinfunction "SCL_24") (pintype "passive"))
    )
    (net (code "87") (name "Net-(U6-SDA)") (class "Default")
      (node (ref "R19") (pin "1") (pinfunction "1_1") (pintype "passive"))
      (node (ref "R40") (pin "1") (pinfunction "1_1") (pintype "passive"))
      (node (ref "U6") (pin "23") (pinfunction "SDA_23") (pintype "passive"))
    )
    (net (code "88") (name "Net-(U7-SCL)") (class "Default")
      (node (ref "R43") (pin "2") (pinfunction "2_2") (pintype "passive"))
      (node (ref "U7") (pin "B3") (pinfunction "SCL_B3") (pintype "passive"))
    )
    (net (code "89") (name "Net-(U7-SDA)") (class "Default")
      (node (ref "R42") (pin "2") (pinfunction "2_2") (pintype "passive"))
      (node (ref "U7") (pin "C3") (pinfunction "SDA_C3") (pintype "passive"))
    )
    (net (code "90") (name "VCC") (class "Default")
      (node (ref "C11") (pin "1") (pinfunction "1_1") (pintype "passive"))
      (node (ref "C12") (pin "1") (pinfunction "1_1") (pintype "passive"))
      (node (ref "L6") (pin "1") (pinfunction "1_1") (pintype "passive"))
      (node (ref "R17") (pin "1") (pinfunction "1_1") (pintype "passive"))
      (node (ref "R34") (pin "1") (pinfunction "1_1") (pintype "passive"))
    )
    (net (code "91") (name "VDD") (class "Default")
      (node (ref "BAT+") (pin "1") (pinfunction "1_1") (pintype "passive"))
      (node (ref "J2") (pin "4") (pinfunction "4_4") (pintype "passive"))
      (node (ref "L3") (pin "2") (pintype "passive"))
    )
    (net (code "92") (name "unconnected-(U2-NC-Pad44)") (class "Default")
      (node (ref "U2") (pin "44") (pinfunction "NC_44") (pintype "passive+no_connect"))
    )
    (net (code "93") (name "unconnected-(U2-NFC1{slash}P0.09-Pad11)") (class "Default")
      (node (ref "U2") (pin "11") (pinfunction "NFC1/P0.09_11") (pintype "passive+no_connect"))
    )
    (net (code "94") (name "unconnected-(U2-NFC2{slash}P0.10-Pad12)") (class "Default")
      (node (ref "U2") (pin "12") (pinfunction "NFC2/P0.10_12") (pintype "passive+no_connect"))
    )
    (net (code "95") (name "unconnected-(U2-P0.24-Pad29)") (class "Default")
      (node (ref "U2") (pin "29") (pinfunction "P0.24_29") (pintype "passive+no_connect"))
    )
    (net (code "96") (name "unconnected-(U2-P0.27-Pad39)") (class "Default")
      (node (ref "U2") (pin "39") (pinfunction "P0.27_39") (pintype "passive+no_connect"))
    )
    (net (code "97") (name "unconnected-(U2-P0.28{slash}AIN4-Pad40)") (class "Default")
      (node (ref "U2") (pin "40") (pinfunction "P0.28/AIN4_40") (pintype "passive+no_connect"))
    )
    (net (code "98") (name "unconnected-(U2-P0.31{slash}AIN7-Pad43)") (class "Default")
      (node (ref "U2") (pin "43") (pinfunction "P0.31/AIN7_43") (pintype "passive+no_connect"))
    )
    (net (code "99") (name "unconnected-(U4-ASCx-Pad3)") (class "Default")
      (node (ref "U4") (pin "3") (pinfunction "ASCx_3") (pintype "passive+no_connect"))
    )
    (net (code "100") (name "unconnected-(U4-ASDx-Pad2)") (class "Default")
      (node (ref "U4") (pin "2") (pinfunction "ASDx_2") (pintype "passive+no_connect"))
    )
    (net (code "101") (name "unconnected-(U4-CSB-Pad12)") (class "Default")
      (node (ref "U4") (pin "12") (pinfunction "CSB_12") (pintype "passive+no_connect"))
    )
    (net (code "102") (name "unconnected-(U4-INT2-Pad9)") (class "Default")
      (node (ref "U4") (pin "9") (pinfunction "INT2_9") (pintype "passive+no_connect"))
    )
    (net (code "103") (name "unconnected-(U4-OSCB-Pad10)") (class "Default")
      (node (ref "U4") (pin "10") (pinfunction "OSCB_10") (pintype "passive+no_connect"))
    )
    (net (code "104") (name "unconnected-(U4-OSDO-Pad11)") (class "Default")
      (node (ref "U4") (pin "11") (pinfunction "OSDO_11") (pintype "passive+no_connect"))
    )
    (net (code "105") (name "unconnected-(U6-NC-Pad1)") (class "Default")
      (node (ref "U6") (pin "1") (pinfunction "NC_1") (pintype "passive+no_connect"))
    )
    (net (code "106") (name "unconnected-(U6-X8-Pad3)") (class "Default")
      (node (ref "U6") (pin "3") (pinfunction "X8_3") (pintype "passive+no_connect"))
    )
    (net (code "107") (name "unconnected-(U6-X9-Pad2)") (class "Default")
      (node (ref "U6") (pin "2") (pinfunction "X9_2") (pintype "passive+no_connect"))
    )
    (net (code "108") (name "unconnected-(U6-Y8{slash}X10-Pad42)") (class "Default")
      (node (ref "U6") (pin "42") (pinfunction "Y8/X10_42") (pintype "passive+no_connect"))
    )
    (net (code "109") (name "unconnected-(U6-Y9{slash}X11-Pad41)") (class "Default")
      (node (ref "U6") (pin "41") (pinfunction "Y9/X11_41") (pintype "passive+no_connect"))
    )
    (net (code "110") (name "unconnected-(U6-Y10{slash}X12-Pad40)") (class "Default")
      (node (ref "U6") (pin "40") (pinfunction "Y10/X12_40") (pintype "passive+no_connect"))
    )
    (net (code "111") (name "unconnected-(U6-Y11{slash}X13-Pad39)") (class "Default")
      (node (ref "U6") (pin "39") (pinfunction "Y11/X13_39") (pintype "passive+no_connect"))
    )
    (net (code "112") (name "unconnected-(U6-Y12-Pad38)") (class "Default")
      (node (ref "U6") (pin "38") (pinfunction "Y12_38") (pintype "passive+no_connect"))
    )
    (net (code "113") (name "unconnected-(U6-Y13-Pad37)") (class "Default")
      (node (ref "U6") (pin "37") (pinfunction "Y13_37") (pintype "passive+no_connect"))
    )
    (net (code "114") (name "unconnected-(U6-Y14-Pad36)") (class "Default")
      (node (ref "U6") (pin "36") (pinfunction "Y14_36") (pintype "passive+no_connect"))
    )
    (net (code "115") (name "unconnected-(U6-Y15-Pad35)") (class "Default")
      (node (ref "U6") (pin "35") (pinfunction "Y15_35") (pintype "passive+no_connect"))
    )
    (net (code "116") (name "unconnected-(U7-TST-PadA3)") (class "Default")
      (node (ref "U7") (pin "A3") (pinfunction "TST_A3") (pintype "passive+no_connect"))
    )
  )
)
